# design.net
KiCad netlist of a schematic drawn in EasyEDA Pro
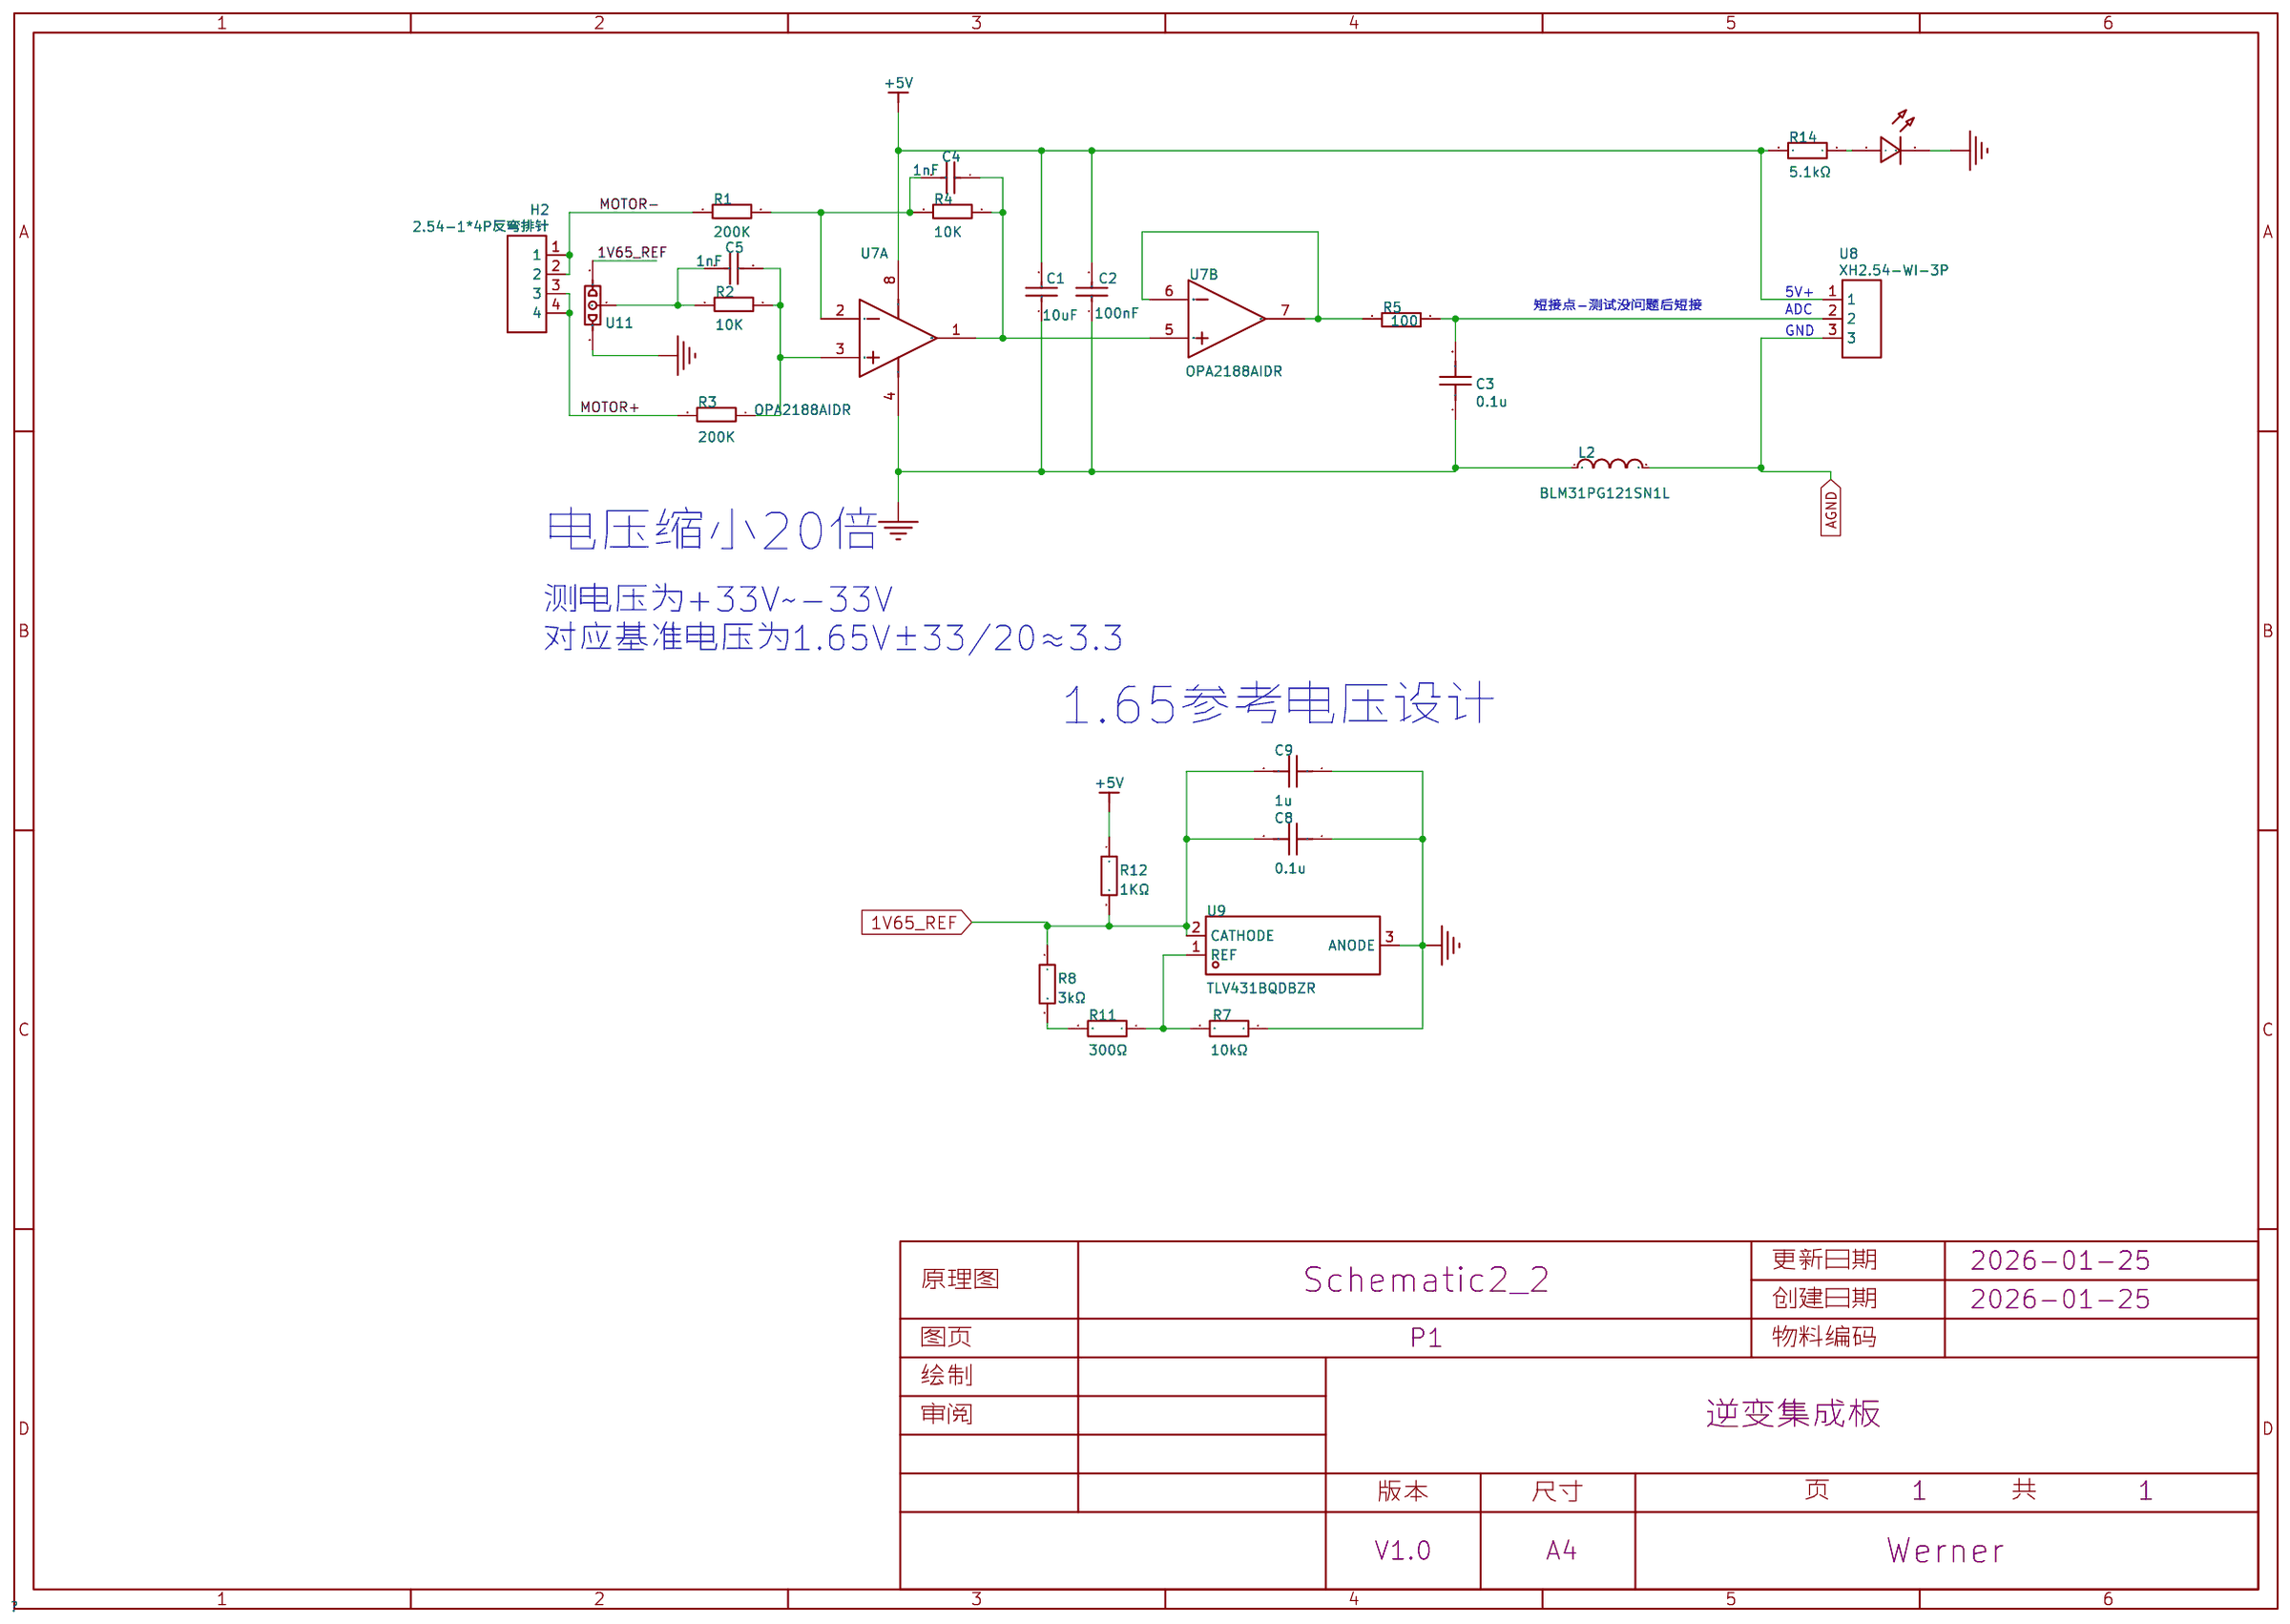
[diagram p0: schematic sheet]

(export (version "E")
  (design (tool "Eeschema 10.0.6"))
  (components
    (comp (ref "1.65V2")
      (value "~")
      (footprint "easyedapro:LED_0603")
      (libsource (lib "easyedapro") (part "LED_R"))
    )
    (comp (ref "C1")
      (value "10uF")
      (footprint "easyedapro:C0805")
      (fields (field (name "Manufacturer Part") "0805B104K500NT") (field (name "Manufacturer") "FH(风华)"))
      (libsource (lib "easyedapro") (part "0805B104K500NT"))
    )
    (comp (ref "C2")
      (value "100nF")
      (footprint "easyedapro:C0805")
      (fields (field (name "Manufacturer Part") "0805B104K500NT") (field (name "Manufacturer") "FH(风华)"))
      (libsource (lib "easyedapro") (part "0805B104K500NT"))
    )
    (comp (ref "C3")
      (value "0.1u")
      (footprint "easyedapro:C0603_2")
      (libsource (lib "easyedapro") (part "0.1u"))
    )
    (comp (ref "C4")
      (value "1nF")
      (footprint "easyedapro:C0805")
      (description "容值:100nF;精度:±10%;额定电压:50V;材质(温度系数):X7R;")
      (fields (field (name "Manufacturer Part") "0805B104K500NT") (field (name "Manufacturer") "FH(风华)"))
      (libsource (lib "easyedapro") (part "0805B104K500NT"))
    )
    (comp (ref "C5")
      (value "1nF")
      (footprint "easyedapro:C0805")
      (description "容值:100nF;精度:±10%;额定电压:50V;材质(温度系数):X7R;")
      (fields (field (name "Manufacturer Part") "0805B104K500NT") (field (name "Manufacturer") "FH(风华)"))
      (libsource (lib "easyedapro") (part "0805B104K500NT"))
    )
    (comp (ref "C8")
      (value "0.1u")
      (footprint "easyedapro:C0603_2")
      (libsource (lib "easyedapro") (part "0.1u"))
    )
    (comp (ref "C9")
      (value "1u")
      (footprint "easyedapro:C0603_2")
      (libsource (lib "easyedapro") (part "0.1u"))
    )
    (comp (ref "H2")
      (value "2.54-1*4P反弯排针")
      (footprint "easyedapro:HDR-TH_4P-P2.54-H-M-W10.4")
      (fields (field (name "Manufacturer") "BOOMELE(博穆精密)"))
      (libsource (lib "easyedapro") (part "2.54-1*4P反弯排针"))
    )
    (comp (ref "L2")
      (value "BLM31PG121SN1L")
      (footprint "easyedapro:L1206")
      (fields (field (name "Manufacturer") "muRata(村田)"))
      (libsource (lib "easyedapro") (part "BLM31PG121SN1L"))
    )
    (comp (ref "R1") (value "200K") (libsource (lib "easyedapro") (part "10K")))
    (comp (ref "R2") (value "10K") (libsource (lib "easyedapro") (part "1K")))
    (comp (ref "R3") (value "200K") (libsource (lib "easyedapro") (part "10K")))
    (comp (ref "R4") (value "10K") (libsource (lib "easyedapro") (part "4.7K")))
    (comp (ref "R5") (value "100") (libsource (lib "easyedapro") (part "4.7K")))
    (comp (ref "R7")
      (value "10kΩ")
      (footprint "easyedapro:R0805")
      (fields
        (field (name "Manufacturer Part") "0805W8F5101T5E")
        (field (name "Manufacturer") "UNI-ROYAL(厚声)")
      )
      (libsource (lib "easyedapro") (part "0805W8F5101T5E"))
    )
    (comp (ref "R8")
      (value "3kΩ")
      (footprint "easyedapro:R0805")
      (fields
        (field (name "Manufacturer Part") "0805W8F5101T5E")
        (field (name "Manufacturer") "UNI-ROYAL(厚声)")
      )
      (libsource (lib "easyedapro") (part "0805W8F5101T5E"))
    )
    (comp (ref "R11")
      (value "300Ω")
      (footprint "easyedapro:R0805")
      (fields
        (field (name "Manufacturer Part") "0805W8F5101T5E")
        (field (name "Manufacturer") "UNI-ROYAL(厚声)")
      )
      (libsource (lib "easyedapro") (part "0805W8F5101T5E"))
    )
    (comp (ref "R12")
      (value "1KΩ")
      (footprint "easyedapro:R0805")
      (fields
        (field (name "Manufacturer Part") "0805W8F5101T5E")
        (field (name "Manufacturer") "UNI-ROYAL(厚声)")
      )
      (libsource (lib "easyedapro") (part "0805W8F5101T5E"))
    )
    (comp (ref "R14")
      (value "5.1kΩ")
      (footprint "easyedapro:R0805")
      (fields
        (field (name "Manufacturer Part") "0805W8F5101T5E")
        (field (name "Manufacturer") "UNI-ROYAL(厚声)")
      )
      (libsource (lib "easyedapro") (part "0805W8F5101T5E"))
    )
    (comp (ref "U7")
      (value "OPA2188AIDR")
      (footprint "easyedapro:SOIC-8_L4.9-W3.9-P1.27-LS6.0-BL_1")
      (fields (field (name "Manufacturer") "TI(德州仪器)"))
      (libsource (lib "easyedapro") (part "OPA2188AIDR"))
    )
    (comp (ref "U8")
      (value "XH2.54-WI-3P")
      (footprint "easyedapro:CONN-TH_XH2.54-WI-3P")
      (libsource (lib "easyedapro") (part "XH2.54-WI-3P"))
    )
    (comp (ref "U9")
      (value "TLV431BQDBZR")
      (footprint "easyedapro:SOT-23-3_L2.9-W1.3-P0.95-LS2.4-BR")
      (fields (field (name "Manufacturer") "TI(德州仪器)"))
      (libsource (lib "easyedapro") (part "TLV431BQDBZR"))
    )
    (comp (ref "U11")
      (value "~")
      (footprint "easyedapro:3P选择焊接点")
      (libsource (lib "easyedapro") (part "3P焊接选择点"))
    )
  )
  (nets
    (net (code "1") (name "+5V") (class "Default")
      (node (ref "C1") (pin "2") (pinfunction "2_2") (pintype "input"))
      (node (ref "C2") (pin "2") (pinfunction "2_2") (pintype "input"))
      (node (ref "R12") (pin "1") (pinfunction "1_1") (pintype "input"))
      (node (ref "R14") (pin "2") (pinfunction "2_2") (pintype "input"))
      (node (ref "U7") (pin "8") (pinfunction "V+_8") (pintype "unspecified"))
      (node (ref "U8") (pin "1") (pinfunction "1_1") (pintype "unspecified"))
    )
    (net (code "2") (name "/MOTOR+") (class "Default")
      (node (ref "H2") (pin "3") (pinfunction "3_3") (pintype "unspecified"))
      (node (ref "H2") (pin "4") (pinfunction "4_4") (pintype "unspecified"))
      (node (ref "R3") (pin "2") (pintype "unspecified"))
    )
    (net (code "3") (name "/MOTOR-") (class "Default")
      (node (ref "H2") (pin "1") (pinfunction "1_1") (pintype "unspecified"))
      (node (ref "H2") (pin "2") (pinfunction "2_2") (pintype "unspecified"))
      (node (ref "R1") (pin "2") (pintype "unspecified"))
    )
    (net (code "4") (name "1V65_REF") (class "Default")
      (node (ref "C8") (pin "2") (pinfunction "2_2") (pintype "unspecified"))
      (node (ref "C9") (pin "2") (pinfunction "2_2") (pintype "unspecified"))
      (node (ref "R12") (pin "2") (pinfunction "2_2") (pintype "input"))
      (node (ref "R8") (pin "1") (pinfunction "1_1") (pintype "input"))
      (node (ref "U11") (pin "1") (pinfunction "1_1") (pintype "input"))
      (node (ref "U9") (pin "2") (pinfunction "CATHODE_2") (pintype "unspecified"))
    )
    (net (code "5") (name "AGND") (class "Default")
      (node (ref "L2") (pin "2") (pinfunction "2_2") (pintype "unspecified"))
      (node (ref "U8") (pin "3") (pinfunction "3_3") (pintype "unspecified"))
    )
    (net (code "6") (name "GND") (class "Default")
      (node (ref "1.65V2") (pin "1") (pinfunction "C_1") (pintype "input"))
      (node (ref "C1") (pin "1") (pinfunction "1_1") (pintype "input"))
      (node (ref "C2") (pin "1") (pinfunction "1_1") (pintype "input"))
      (node (ref "C3") (pin "1") (pinfunction "1_1") (pintype "unspecified"))
      (node (ref "C8") (pin "1") (pinfunction "1_1") (pintype "unspecified"))
      (node (ref "C9") (pin "1") (pinfunction "1_1") (pintype "unspecified"))
      (node (ref "L2") (pin "1") (pinfunction "1_1") (pintype "unspecified"))
      (node (ref "R7") (pin "1") (pinfunction "1_1") (pintype "input"))
      (node (ref "U11") (pin "3") (pinfunction "3_3") (pintype "input"))
      (node (ref "U7") (pin "4") (pinfunction "V-_4") (pintype "unspecified"))
      (node (ref "U9") (pin "3") (pinfunction "ANODE_3") (pintype "unspecified"))
    )
    (net (code "7") (name "Net-(1.65V2-A)") (class "Default")
      (node (ref "1.65V2") (pin "2") (pinfunction "A_2") (pintype "input"))
      (node (ref "R14") (pin "1") (pinfunction "1_1") (pintype "input"))
    )
    (net (code "8") (name "Net-(C3-Pad2)") (class "Default")
      (node (ref "C3") (pin "2") (pinfunction "2_2") (pintype "unspecified"))
      (node (ref "R5") (pin "2") (pintype "unspecified"))
      (node (ref "U8") (pin "2") (pinfunction "2_2") (pintype "unspecified"))
    )
    (net (code "9") (name "Net-(C5-Pad2)") (class "Default")
      (node (ref "C5") (pin "2") (pinfunction "2_2") (pintype "input"))
      (node (ref "R2") (pin "2") (pintype "unspecified"))
      (node (ref "U11") (pin "2") (pinfunction "2_2") (pintype "input"))
    )
    (net (code "10") (name "Net-(R11-Pad2)") (class "Default")
      (node (ref "R11") (pin "2") (pinfunction "2_2") (pintype "input"))
      (node (ref "R8") (pin "2") (pinfunction "2_2") (pintype "input"))
    )
    (net (code "11") (name "Net-(U7A-IN_A+)") (class "Default")
      (node (ref "C5") (pin "1") (pinfunction "1_1") (pintype "input"))
      (node (ref "R2") (pin "1") (pintype "unspecified"))
      (node (ref "R3") (pin "1") (pintype "unspecified"))
      (node (ref "U7") (pin "3") (pinfunction "IN_A+_3") (pintype "unspecified"))
    )
    (net (code "12") (name "Net-(U7A-IN_A-)") (class "Default")
      (node (ref "C4") (pin "2") (pinfunction "2_2") (pintype "input"))
      (node (ref "R1") (pin "1") (pintype "unspecified"))
      (node (ref "R4") (pin "2") (pintype "unspecified"))
      (node (ref "U7") (pin "2") (pinfunction "IN_A-_2") (pintype "unspecified"))
    )
    (net (code "13") (name "Net-(U7A-OUT_A)") (class "Default")
      (node (ref "C4") (pin "1") (pinfunction "1_1") (pintype "input"))
      (node (ref "R4") (pin "1") (pintype "unspecified"))
      (node (ref "U7") (pin "1") (pinfunction "OUT_A_1") (pintype "output"))
      (node (ref "U7") (pin "5") (pinfunction "IN_B+_5") (pintype "unspecified"))
    )
    (net (code "14") (name "Net-(U7B-IN_B-)") (class "Default")
      (node (ref "R5") (pin "1") (pintype "unspecified"))
      (node (ref "U7") (pin "6") (pinfunction "IN_B-_6") (pintype "unspecified"))
      (node (ref "U7") (pin "7") (pinfunction "OUT_B_7") (pintype "output"))
    )
    (net (code "15") (name "Net-(U9-REF)") (class "Default")
      (node (ref "R11") (pin "1") (pinfunction "1_1") (pintype "input"))
      (node (ref "R7") (pin "2") (pinfunction "2_2") (pintype "input"))
      (node (ref "U9") (pin "1") (pinfunction "REF_1") (pintype "unspecified"))
    )
  )
)
